# S05-INTERFACES.net
KiCad netlist of a schematic drawn in Altium Designer
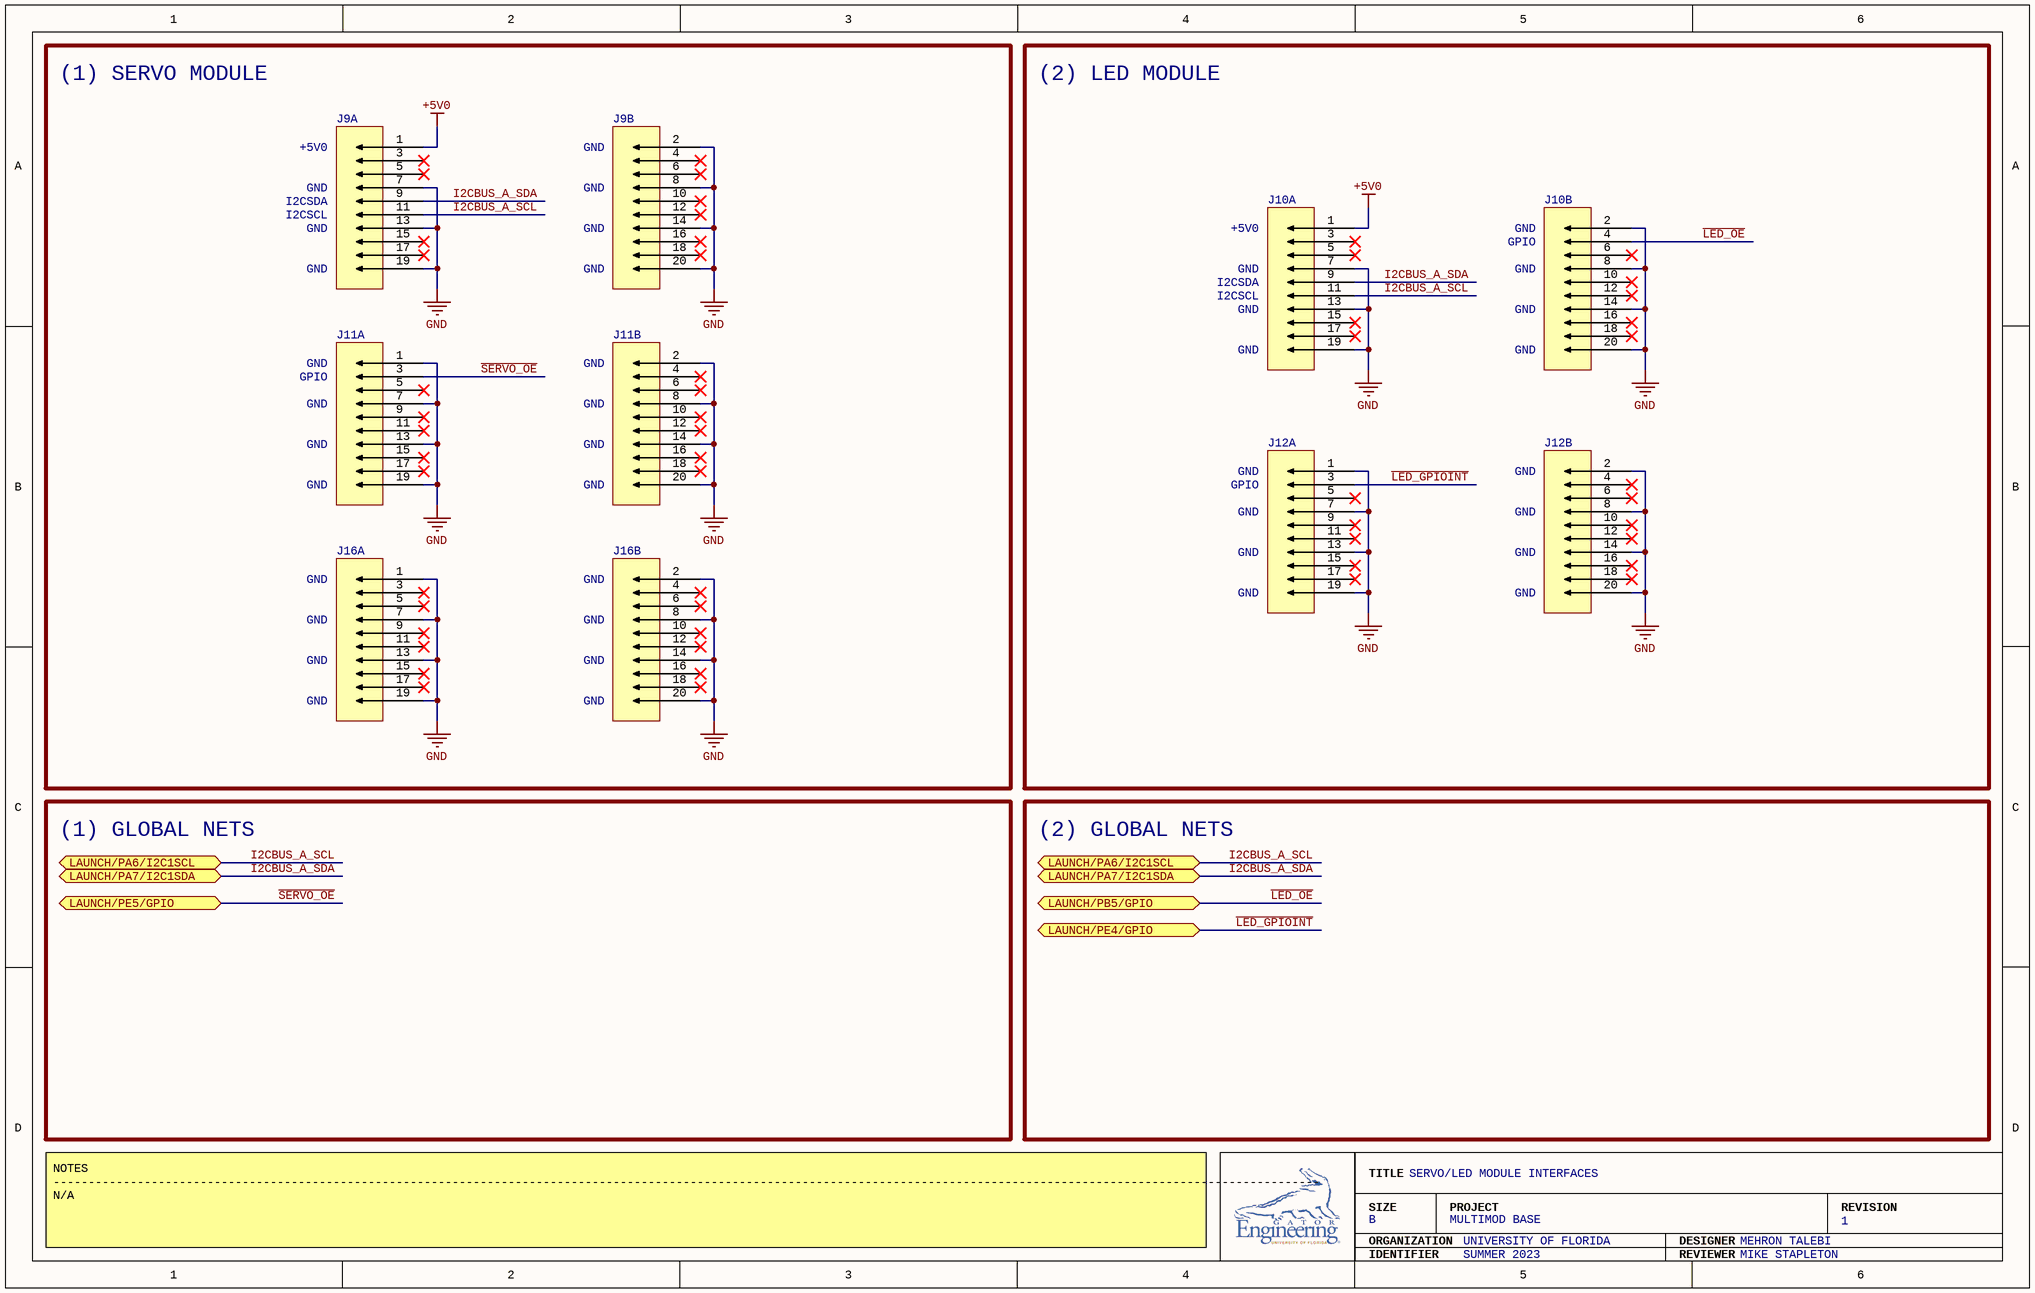
[diagram p0: S05-INTERFACES.SchDoc]

(export (version "E")
  (design (tool "Eeschema 10.0.6"))
  (components
    (comp (ref "J9")
      (value "95278-101-20LF")
      (footprint "95278-101-20LF")
      (description "CONN HEADER SMD 20POS 2.54MM")
      (libsource (lib "Master") (part "95278-101-20LF"))
    )
    (comp (ref "J10")
      (value "95278-101-20LF")
      (footprint "95278-101-20LF")
      (description "CONN HEADER SMD 20POS 2.54MM")
      (libsource (lib "Master") (part "95278-101-20LF"))
    )
    (comp (ref "J11")
      (value "95278-101-20LF")
      (footprint "95278-101-20LF")
      (description "CONN HEADER SMD 20POS 2.54MM")
      (libsource (lib "Master") (part "95278-101-20LF"))
    )
    (comp (ref "J12")
      (value "95278-101-20LF")
      (footprint "95278-101-20LF")
      (description "CONN HEADER SMD 20POS 2.54MM")
      (libsource (lib "Master") (part "95278-101-20LF"))
    )
    (comp (ref "J16")
      (value "95278-101-20LF")
      (footprint "95278-101-20LF")
      (description "CONN HEADER SMD 20POS 2.54MM")
      (libsource (lib "Master") (part "95278-101-20LF"))
    )
  )
  (nets
    (net (code "1") (name "+5V0") (class "Default")
      (node (ref "J10") (pin "1") (pinfunction "1_1") (pintype "passive"))
      (node (ref "J9") (pin "1") (pinfunction "1_1") (pintype "passive"))
    )
    (net (code "2") (name "/I2CBUS_A_SCL") (class "Default")
      (node (ref "J10") (pin "11") (pinfunction "11_11") (pintype "passive"))
      (node (ref "J9") (pin "11") (pinfunction "11_11") (pintype "passive"))
    )
    (net (code "3") (name "/I2CBUS_A_SDA") (class "Default")
      (node (ref "J10") (pin "9") (pinfunction "9_9") (pintype "passive"))
      (node (ref "J9") (pin "9") (pinfunction "9_9") (pintype "passive"))
    )
    (net (code "4") (name "/LED_GPIOINT") (class "Default")
      (node (ref "J12") (pin "3") (pinfunction "3_3") (pintype "passive"))
    )
    (net (code "5") (name "/LED_OE") (class "Default")
      (node (ref "J10") (pin "4") (pinfunction "4_4") (pintype "passive"))
    )
    (net (code "6") (name "/SERVO_OE") (class "Default")
      (node (ref "J11") (pin "3") (pinfunction "3_3") (pintype "passive"))
    )
    (net (code "7") (name "GND") (class "Default")
      (node (ref "J10") (pin "13") (pinfunction "13_13") (pintype "passive"))
      (node (ref "J10") (pin "14") (pinfunction "14_14") (pintype "passive"))
      (node (ref "J10") (pin "19") (pinfunction "19_19") (pintype "passive"))
      (node (ref "J10") (pin "2") (pinfunction "2_2") (pintype "passive"))
      (node (ref "J10") (pin "20") (pinfunction "20_20") (pintype "passive"))
      (node (ref "J10") (pin "7") (pinfunction "7_7") (pintype "passive"))
      (node (ref "J10") (pin "8") (pinfunction "8_8") (pintype "passive"))
      (node (ref "J11") (pin "1") (pinfunction "1_1") (pintype "passive"))
      (node (ref "J11") (pin "13") (pinfunction "13_13") (pintype "passive"))
      (node (ref "J11") (pin "14") (pinfunction "14_14") (pintype "passive"))
      (node (ref "J11") (pin "19") (pinfunction "19_19") (pintype "passive"))
      (node (ref "J11") (pin "2") (pinfunction "2_2") (pintype "passive"))
      (node (ref "J11") (pin "20") (pinfunction "20_20") (pintype "passive"))
      (node (ref "J11") (pin "7") (pinfunction "7_7") (pintype "passive"))
      (node (ref "J11") (pin "8") (pinfunction "8_8") (pintype "passive"))
      (node (ref "J12") (pin "1") (pinfunction "1_1") (pintype "passive"))
      (node (ref "J12") (pin "13") (pinfunction "13_13") (pintype "passive"))
      (node (ref "J12") (pin "14") (pinfunction "14_14") (pintype "passive"))
      (node (ref "J12") (pin "19") (pinfunction "19_19") (pintype "passive"))
      (node (ref "J12") (pin "2") (pinfunction "2_2") (pintype "passive"))
      (node (ref "J12") (pin "20") (pinfunction "20_20") (pintype "passive"))
      (node (ref "J12") (pin "7") (pinfunction "7_7") (pintype "passive"))
      (node (ref "J12") (pin "8") (pinfunction "8_8") (pintype "passive"))
      (node (ref "J16") (pin "1") (pinfunction "1_1") (pintype "passive"))
      (node (ref "J16") (pin "13") (pinfunction "13_13") (pintype "passive"))
      (node (ref "J16") (pin "14") (pinfunction "14_14") (pintype "passive"))
      (node (ref "J16") (pin "19") (pinfunction "19_19") (pintype "passive"))
      (node (ref "J16") (pin "2") (pinfunction "2_2") (pintype "passive"))
      (node (ref "J16") (pin "20") (pinfunction "20_20") (pintype "passive"))
      (node (ref "J16") (pin "7") (pinfunction "7_7") (pintype "passive"))
      (node (ref "J16") (pin "8") (pinfunction "8_8") (pintype "passive"))
      (node (ref "J9") (pin "13") (pinfunction "13_13") (pintype "passive"))
      (node (ref "J9") (pin "14") (pinfunction "14_14") (pintype "passive"))
      (node (ref "J9") (pin "19") (pinfunction "19_19") (pintype "passive"))
      (node (ref "J9") (pin "2") (pinfunction "2_2") (pintype "passive"))
      (node (ref "J9") (pin "20") (pinfunction "20_20") (pintype "passive"))
      (node (ref "J9") (pin "7") (pinfunction "7_7") (pintype "passive"))
      (node (ref "J9") (pin "8") (pinfunction "8_8") (pintype "passive"))
    )
    (net (code "8") (name "unconnected-(J9-Pad3)") (class "Default")
      (node (ref "J9") (pin "3") (pinfunction "3_3") (pintype "passive+no_connect"))
    )
    (net (code "9") (name "unconnected-(J9-Pad4)") (class "Default")
      (node (ref "J9") (pin "4") (pinfunction "4_4") (pintype "passive+no_connect"))
    )
    (net (code "10") (name "unconnected-(J9-Pad5)") (class "Default")
      (node (ref "J9") (pin "5") (pinfunction "5_5") (pintype "passive+no_connect"))
    )
    (net (code "11") (name "unconnected-(J9-Pad6)") (class "Default")
      (node (ref "J9") (pin "6") (pinfunction "6_6") (pintype "passive+no_connect"))
    )
    (net (code "12") (name "unconnected-(J9-Pad10)") (class "Default")
      (node (ref "J9") (pin "10") (pinfunction "10_10") (pintype "passive+no_connect"))
    )
    (net (code "13") (name "unconnected-(J9-Pad12)") (class "Default")
      (node (ref "J9") (pin "12") (pinfunction "12_12") (pintype "passive+no_connect"))
    )
    (net (code "14") (name "unconnected-(J9-Pad15)") (class "Default")
      (node (ref "J9") (pin "15") (pinfunction "15_15") (pintype "passive+no_connect"))
    )
    (net (code "15") (name "unconnected-(J9-Pad16)") (class "Default")
      (node (ref "J9") (pin "16") (pinfunction "16_16") (pintype "passive+no_connect"))
    )
    (net (code "16") (name "unconnected-(J9-Pad17)") (class "Default")
      (node (ref "J9") (pin "17") (pinfunction "17_17") (pintype "passive+no_connect"))
    )
    (net (code "17") (name "unconnected-(J9-Pad18)") (class "Default")
      (node (ref "J9") (pin "18") (pinfunction "18_18") (pintype "passive+no_connect"))
    )
    (net (code "18") (name "unconnected-(J10-Pad3)") (class "Default")
      (node (ref "J10") (pin "3") (pinfunction "3_3") (pintype "passive+no_connect"))
    )
    (net (code "19") (name "unconnected-(J10-Pad5)") (class "Default")
      (node (ref "J10") (pin "5") (pinfunction "5_5") (pintype "passive+no_connect"))
    )
    (net (code "20") (name "unconnected-(J10-Pad6)") (class "Default")
      (node (ref "J10") (pin "6") (pinfunction "6_6") (pintype "passive+no_connect"))
    )
    (net (code "21") (name "unconnected-(J10-Pad10)") (class "Default")
      (node (ref "J10") (pin "10") (pinfunction "10_10") (pintype "passive+no_connect"))
    )
    (net (code "22") (name "unconnected-(J10-Pad12)") (class "Default")
      (node (ref "J10") (pin "12") (pinfunction "12_12") (pintype "passive+no_connect"))
    )
    (net (code "23") (name "unconnected-(J10-Pad15)") (class "Default")
      (node (ref "J10") (pin "15") (pinfunction "15_15") (pintype "passive+no_connect"))
    )
    (net (code "24") (name "unconnected-(J10-Pad16)") (class "Default")
      (node (ref "J10") (pin "16") (pinfunction "16_16") (pintype "passive+no_connect"))
    )
    (net (code "25") (name "unconnected-(J10-Pad17)") (class "Default")
      (node (ref "J10") (pin "17") (pinfunction "17_17") (pintype "passive+no_connect"))
    )
    (net (code "26") (name "unconnected-(J10-Pad18)") (class "Default")
      (node (ref "J10") (pin "18") (pinfunction "18_18") (pintype "passive+no_connect"))
    )
    (net (code "27") (name "unconnected-(J11-Pad4)") (class "Default")
      (node (ref "J11") (pin "4") (pinfunction "4_4") (pintype "passive+no_connect"))
    )
    (net (code "28") (name "unconnected-(J11-Pad5)") (class "Default")
      (node (ref "J11") (pin "5") (pinfunction "5_5") (pintype "passive+no_connect"))
    )
    (net (code "29") (name "unconnected-(J11-Pad6)") (class "Default")
      (node (ref "J11") (pin "6") (pinfunction "6_6") (pintype "passive+no_connect"))
    )
    (net (code "30") (name "unconnected-(J11-Pad9)") (class "Default")
      (node (ref "J11") (pin "9") (pinfunction "9_9") (pintype "passive+no_connect"))
    )
    (net (code "31") (name "unconnected-(J11-Pad10)") (class "Default")
      (node (ref "J11") (pin "10") (pinfunction "10_10") (pintype "passive+no_connect"))
    )
    (net (code "32") (name "unconnected-(J11-Pad11)") (class "Default")
      (node (ref "J11") (pin "11") (pinfunction "11_11") (pintype "passive+no_connect"))
    )
    (net (code "33") (name "unconnected-(J11-Pad12)") (class "Default")
      (node (ref "J11") (pin "12") (pinfunction "12_12") (pintype "passive+no_connect"))
    )
    (net (code "34") (name "unconnected-(J11-Pad15)") (class "Default")
      (node (ref "J11") (pin "15") (pinfunction "15_15") (pintype "passive+no_connect"))
    )
    (net (code "35") (name "unconnected-(J11-Pad16)") (class "Default")
      (node (ref "J11") (pin "16") (pinfunction "16_16") (pintype "passive+no_connect"))
    )
    (net (code "36") (name "unconnected-(J11-Pad17)") (class "Default")
      (node (ref "J11") (pin "17") (pinfunction "17_17") (pintype "passive+no_connect"))
    )
    (net (code "37") (name "unconnected-(J11-Pad18)") (class "Default")
      (node (ref "J11") (pin "18") (pinfunction "18_18") (pintype "passive+no_connect"))
    )
    (net (code "38") (name "unconnected-(J12-Pad4)") (class "Default")
      (node (ref "J12") (pin "4") (pinfunction "4_4") (pintype "passive+no_connect"))
    )
    (net (code "39") (name "unconnected-(J12-Pad5)") (class "Default")
      (node (ref "J12") (pin "5") (pinfunction "5_5") (pintype "passive+no_connect"))
    )
    (net (code "40") (name "unconnected-(J12-Pad6)") (class "Default")
      (node (ref "J12") (pin "6") (pinfunction "6_6") (pintype "passive+no_connect"))
    )
    (net (code "41") (name "unconnected-(J12-Pad9)") (class "Default")
      (node (ref "J12") (pin "9") (pinfunction "9_9") (pintype "passive+no_connect"))
    )
    (net (code "42") (name "unconnected-(J12-Pad10)") (class "Default")
      (node (ref "J12") (pin "10") (pinfunction "10_10") (pintype "passive+no_connect"))
    )
    (net (code "43") (name "unconnected-(J12-Pad11)") (class "Default")
      (node (ref "J12") (pin "11") (pinfunction "11_11") (pintype "passive+no_connect"))
    )
    (net (code "44") (name "unconnected-(J12-Pad12)") (class "Default")
      (node (ref "J12") (pin "12") (pinfunction "12_12") (pintype "passive+no_connect"))
    )
    (net (code "45") (name "unconnected-(J12-Pad15)") (class "Default")
      (node (ref "J12") (pin "15") (pinfunction "15_15") (pintype "passive+no_connect"))
    )
    (net (code "46") (name "unconnected-(J12-Pad16)") (class "Default")
      (node (ref "J12") (pin "16") (pinfunction "16_16") (pintype "passive+no_connect"))
    )
    (net (code "47") (name "unconnected-(J12-Pad17)") (class "Default")
      (node (ref "J12") (pin "17") (pinfunction "17_17") (pintype "passive+no_connect"))
    )
    (net (code "48") (name "unconnected-(J12-Pad18)") (class "Default")
      (node (ref "J12") (pin "18") (pinfunction "18_18") (pintype "passive+no_connect"))
    )
    (net (code "49") (name "unconnected-(J16-Pad3)") (class "Default")
      (node (ref "J16") (pin "3") (pinfunction "3_3") (pintype "passive+no_connect"))
    )
    (net (code "50") (name "unconnected-(J16-Pad4)") (class "Default")
      (node (ref "J16") (pin "4") (pinfunction "4_4") (pintype "passive+no_connect"))
    )
    (net (code "51") (name "unconnected-(J16-Pad5)") (class "Default")
      (node (ref "J16") (pin "5") (pinfunction "5_5") (pintype "passive+no_connect"))
    )
    (net (code "52") (name "unconnected-(J16-Pad6)") (class "Default")
      (node (ref "J16") (pin "6") (pinfunction "6_6") (pintype "passive+no_connect"))
    )
    (net (code "53") (name "unconnected-(J16-Pad9)") (class "Default")
      (node (ref "J16") (pin "9") (pinfunction "9_9") (pintype "passive+no_connect"))
    )
    (net (code "54") (name "unconnected-(J16-Pad10)") (class "Default")
      (node (ref "J16") (pin "10") (pinfunction "10_10") (pintype "passive+no_connect"))
    )
    (net (code "55") (name "unconnected-(J16-Pad11)") (class "Default")
      (node (ref "J16") (pin "11") (pinfunction "11_11") (pintype "passive+no_connect"))
    )
    (net (code "56") (name "unconnected-(J16-Pad12)") (class "Default")
      (node (ref "J16") (pin "12") (pinfunction "12_12") (pintype "passive+no_connect"))
    )
    (net (code "57") (name "unconnected-(J16-Pad15)") (class "Default")
      (node (ref "J16") (pin "15") (pinfunction "15_15") (pintype "passive+no_connect"))
    )
    (net (code "58") (name "unconnected-(J16-Pad16)") (class "Default")
      (node (ref "J16") (pin "16") (pinfunction "16_16") (pintype "passive+no_connect"))
    )
    (net (code "59") (name "unconnected-(J16-Pad17)") (class "Default")
      (node (ref "J16") (pin "17") (pinfunction "17_17") (pintype "passive+no_connect"))
    )
    (net (code "60") (name "unconnected-(J16-Pad18)") (class "Default")
      (node (ref "J16") (pin "18") (pinfunction "18_18") (pintype "passive+no_connect"))
    )
  )
)
